# left_revision3_1.net
KiCad netlist of a schematic drawn in EAGLE
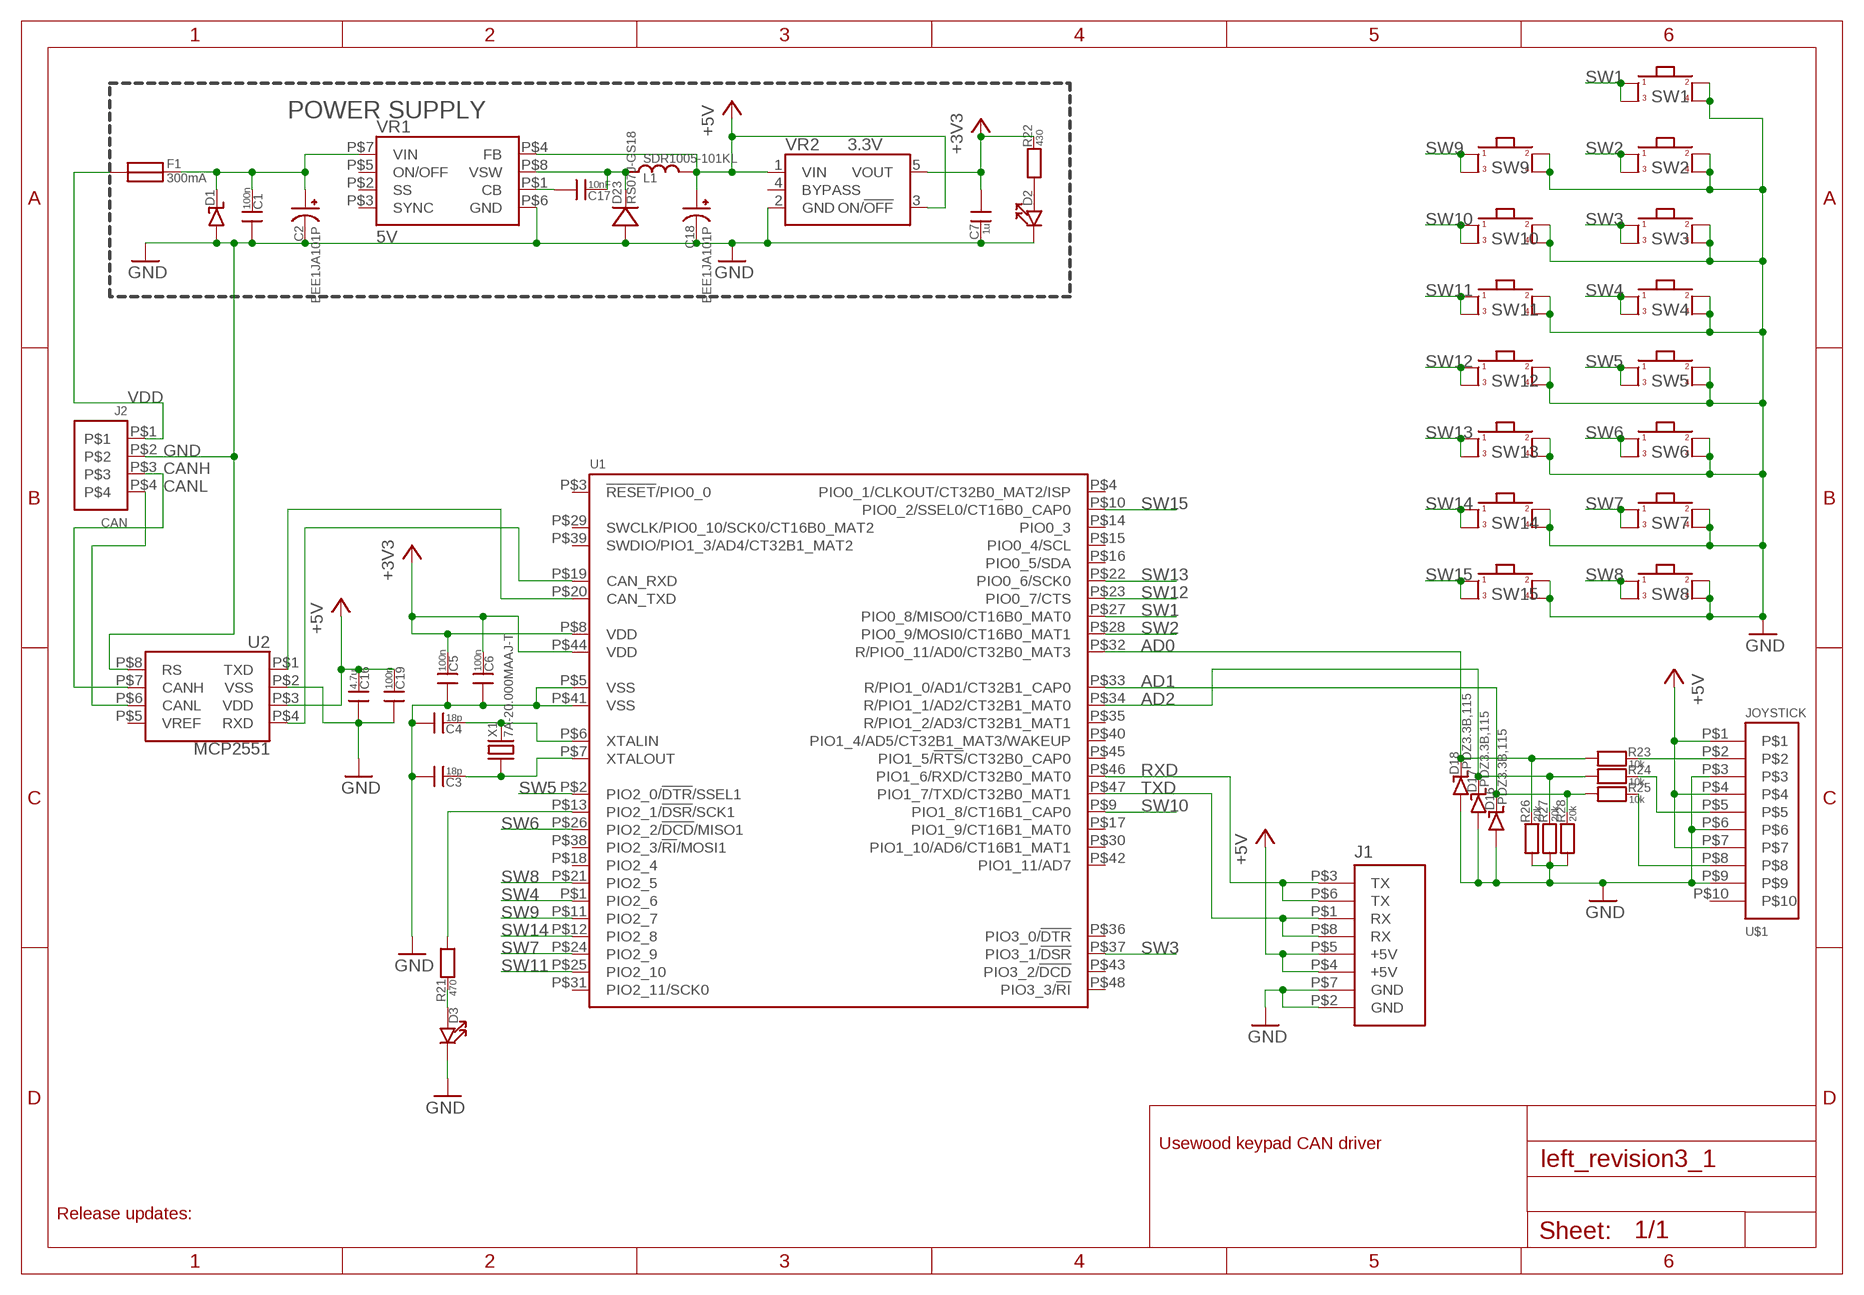
[diagram p0: schematic, sheet 1]

(export (version "E")
  (design (tool "Eeschema 10.0.6"))
  (components
    (comp (ref "C1")
      (value "100n")
      (footprint "eagle-import:0603_SILKSCREEN")
      (libsource (lib "eagle-import") (part "CAP_0603"))
    )
    (comp (ref "C2")
      (value "EEE1JA101P")
      (footprint "eagle-import:CAP_POL_SMD_10X10X10MM")
      (libsource (lib "eagle-import") (part "CAP_POLSMD_10X10X10MM"))
    )
    (comp (ref "C3")
      (value "18p")
      (footprint "eagle-import:0603_SILKSCREEN")
      (libsource (lib "eagle-import") (part "CAP_0603"))
    )
    (comp (ref "C4")
      (value "18p")
      (footprint "eagle-import:0603_SILKSCREEN")
      (libsource (lib "eagle-import") (part "CAP_0603"))
    )
    (comp (ref "C5")
      (value "100n")
      (footprint "eagle-import:0603_SILKSCREEN")
      (libsource (lib "eagle-import") (part "CAP_0603"))
    )
    (comp (ref "C6")
      (value "100n")
      (footprint "eagle-import:0603_SILKSCREEN")
      (libsource (lib "eagle-import") (part "CAP_0603"))
    )
    (comp (ref "C7")
      (value "1u")
      (footprint "eagle-import:0603_SILKSCREEN")
      (libsource (lib "eagle-import") (part "CAP_0603"))
    )
    (comp (ref "C16")
      (value "4.7u")
      (footprint "eagle-import:0603_SILKSCREEN")
      (libsource (lib "eagle-import") (part "CAP_0603"))
    )
    (comp (ref "C17")
      (value "10nF")
      (footprint "eagle-import:0603_SILKSCREEN")
      (libsource (lib "eagle-import") (part "CAP_0603"))
    )
    (comp (ref "C18")
      (value "EEE1JA101P")
      (footprint "eagle-import:CAP_POL_SMD_10X10X10MM")
      (libsource (lib "eagle-import") (part "CAP_POLSMD_10X10X10MM"))
    )
    (comp (ref "C19")
      (value "100n")
      (footprint "eagle-import:0603_SILKSCREEN")
      (libsource (lib "eagle-import") (part "CAP_0603"))
    )
    (comp (ref "D1")
      (value "DIODE_TVSDO-214AA")
      (footprint "eagle-import:DO-214AB")
      (libsource (lib "eagle-import") (part "DIODE_TVSDO-214AA"))
    )
    (comp (ref "D2")
      (value "LED_0603")
      (footprint "eagle-import:0603_SILKSCREEN")
      (libsource (lib "eagle-import") (part "LED_0603"))
    )
    (comp (ref "D3")
      (value "LED_0603")
      (footprint "eagle-import:0603_SILKSCREEN")
      (libsource (lib "eagle-import") (part "LED_0603"))
    )
    (comp (ref "D16")
      (value "PDZ3.3B,115")
      (footprint "eagle-import:SOD123")
      (libsource (lib "eagle-import") (part "DIODE_ZENERSDO123"))
    )
    (comp (ref "D17")
      (value "PDZ3.3B,115")
      (footprint "eagle-import:SOD123")
      (libsource (lib "eagle-import") (part "DIODE_ZENERSDO123"))
    )
    (comp (ref "D18")
      (value "PDZ3.3B,115")
      (footprint "eagle-import:SOD123")
      (libsource (lib "eagle-import") (part "DIODE_ZENERSDO123"))
    )
    (comp (ref "D23")
      (value "RS07J-GS18")
      (footprint "eagle-import:DO219AB")
      (libsource (lib "eagle-import") (part "DIODEDO219AB"))
    )
    (comp (ref "F1")
      (value "300mA")
      (footprint "eagle-import:FUSE_100MA")
      (libsource (lib "eagle-import") (part "FUSE_MC36204_100MA"))
    )
    (comp (ref "J1")
      (value "HEADER_USART_2_SMD")
      (footprint "eagle-import:HEADER_4_2_SMD")
      (libsource (lib "eagle-import") (part "HEADER_USART_2_SMD"))
    )
    (comp (ref "J2")
      (value "CAN")
      (footprint "eagle-import:MOLEX_MICRO_FIT_4WAY_SMD")
      (libsource (lib "eagle-import") (part "MOLEX_MICRO-FIT_4WAY_SMD"))
    )
    (comp (ref "L1")
      (value "SDR1005-101KL")
      (footprint "eagle-import:INDUCTOR_BOURNS_10X13X5MM")
      (libsource (lib "eagle-import") (part "INDUCTORBOURNS_10X13X5MM"))
    )
    (comp (ref "R21")
      (value "470")
      (footprint "eagle-import:0603_SILKSCREEN")
      (libsource (lib "eagle-import") (part "RES_0603"))
    )
    (comp (ref "R22")
      (value "430")
      (footprint "eagle-import:0603_SILKSCREEN")
      (libsource (lib "eagle-import") (part "RES_0603"))
    )
    (comp (ref "R23")
      (value "10k")
      (footprint "eagle-import:0603_SILKSCREEN")
      (libsource (lib "eagle-import") (part "RES_0603"))
    )
    (comp (ref "R24")
      (value "10k")
      (footprint "eagle-import:0603_SILKSCREEN")
      (libsource (lib "eagle-import") (part "RES_0603"))
    )
    (comp (ref "R25")
      (value "10k")
      (footprint "eagle-import:0603_SILKSCREEN")
      (libsource (lib "eagle-import") (part "RES_0603"))
    )
    (comp (ref "R26")
      (value "20k")
      (footprint "eagle-import:0603_SILKSCREEN")
      (libsource (lib "eagle-import") (part "RES_0603"))
    )
    (comp (ref "R27")
      (value "20k")
      (footprint "eagle-import:0603_SILKSCREEN")
      (libsource (lib "eagle-import") (part "RES_0603"))
    )
    (comp (ref "R28")
      (value "20k")
      (footprint "eagle-import:0603_SILKSCREEN")
      (libsource (lib "eagle-import") (part "RES_0603"))
    )
    (comp (ref "SW1")
      (value "SWITCH_KMR231G")
      (footprint "eagle-import:SWITCH_KMR231")
      (libsource (lib "eagle-import") (part "SWITCH_KMR231G"))
    )
    (comp (ref "SW2")
      (value "SWITCH_KMR231G")
      (footprint "eagle-import:SWITCH_KMR231")
      (libsource (lib "eagle-import") (part "SWITCH_KMR231G"))
    )
    (comp (ref "SW3")
      (value "SWITCH_KMR231G")
      (footprint "eagle-import:SWITCH_KMR231")
      (libsource (lib "eagle-import") (part "SWITCH_KMR231G"))
    )
    (comp (ref "SW4")
      (value "SWITCH_KMR231G")
      (footprint "eagle-import:SWITCH_KMR231")
      (libsource (lib "eagle-import") (part "SWITCH_KMR231G"))
    )
    (comp (ref "SW5")
      (value "SWITCH_KMR231G")
      (footprint "eagle-import:SWITCH_KMR231")
      (libsource (lib "eagle-import") (part "SWITCH_KMR231G"))
    )
    (comp (ref "SW6")
      (value "SWITCH_KMR231G")
      (footprint "eagle-import:SWITCH_KMR231")
      (libsource (lib "eagle-import") (part "SWITCH_KMR231G"))
    )
    (comp (ref "SW7")
      (value "SWITCH_KMR231G")
      (footprint "eagle-import:SWITCH_KMR231")
      (libsource (lib "eagle-import") (part "SWITCH_KMR231G"))
    )
    (comp (ref "SW8")
      (value "SWITCH_KMR231G")
      (footprint "eagle-import:SWITCH_KMR231")
      (libsource (lib "eagle-import") (part "SWITCH_KMR231G"))
    )
    (comp (ref "SW9")
      (value "SWITCH_KMR231G")
      (footprint "eagle-import:SWITCH_KMR231")
      (libsource (lib "eagle-import") (part "SWITCH_KMR231G"))
    )
    (comp (ref "SW10")
      (value "SWITCH_KMR231G")
      (footprint "eagle-import:SWITCH_KMR231")
      (libsource (lib "eagle-import") (part "SWITCH_KMR231G"))
    )
    (comp (ref "SW11")
      (value "SWITCH_KMR231G")
      (footprint "eagle-import:SWITCH_KMR231")
      (libsource (lib "eagle-import") (part "SWITCH_KMR231G"))
    )
    (comp (ref "SW12")
      (value "SWITCH_KMR231G")
      (footprint "eagle-import:SWITCH_KMR231")
      (libsource (lib "eagle-import") (part "SWITCH_KMR231G"))
    )
    (comp (ref "SW13")
      (value "SWITCH_KMR231G")
      (footprint "eagle-import:SWITCH_KMR231")
      (libsource (lib "eagle-import") (part "SWITCH_KMR231G"))
    )
    (comp (ref "SW14")
      (value "SWITCH_KMR231G")
      (footprint "eagle-import:SWITCH_KMR231")
      (libsource (lib "eagle-import") (part "SWITCH_KMR231G"))
    )
    (comp (ref "SW15")
      (value "SWITCH_KMR231G")
      (footprint "eagle-import:SWITCH_KMR231")
      (libsource (lib "eagle-import") (part "SWITCH_KMR231G"))
    )
    (comp (ref "U$1")
      (value "JOYSTICK")
      (footprint "eagle-import:MOLEX_MICRO_FIT_10WAY_SMD")
      (libsource (lib "eagle-import") (part "MOLEX_MICRO-FIT_10WAY_SMD"))
    )
    (comp (ref "U1")
      (value "LPC11C14_QFP48")
      (footprint "eagle-import:QFP48")
      (libsource (lib "eagle-import") (part "LPC11C14_QFP48"))
    )
    (comp (ref "U2")
      (value "MCP2551")
      (footprint "eagle-import:SOIC8")
      (libsource (lib "eagle-import") (part "MCP2551_SOIC8"))
    )
    (comp (ref "VR1")
      (value "5V")
      (footprint "eagle-import:SOIC8")
      (libsource (lib "eagle-import") (part "LM2671SOIC8"))
    )
    (comp (ref "VR2")
      (value "3.3V")
      (footprint "eagle-import:SOP5")
      (libsource (lib "eagle-import") (part "REG_LP2985_SOP5"))
    )
    (comp (ref "X1")
      (value "7A-20.000MAAJ-T")
      (footprint "eagle-import:XTAL_SMD_5X3.2")
      (libsource (lib "eagle-import") (part "XTAL_7A-12.000MAAJ-T"))
    )
  )
  (nets
    (net (code "1") (name "+3V3") (class "Default")
      (node (ref "C5") (pin "1") (pinfunction "P$2_1") (pintype "bidirectional"))
      (node (ref "C6") (pin "1") (pinfunction "P$2_1") (pintype "bidirectional"))
      (node (ref "C7") (pin "0") (pinfunction "P$1_0") (pintype "bidirectional"))
      (node (ref "R22") (pin "1") (pinfunction "P$2_1") (pintype "bidirectional"))
      (node (ref "U1") (pin "P$44") (pinfunction "VDD_P$44") (pintype "bidirectional"))
      (node (ref "U1") (pin "P$8") (pinfunction "VDD_P$8") (pintype "bidirectional"))
      (node (ref "VR2") (pin "5") (pinfunction "VOUT_5") (pintype "bidirectional"))
    )
    (net (code "2") (name "+5V") (class "Default")
      (node (ref "C16") (pin "1") (pinfunction "P$2_1") (pintype "bidirectional"))
      (node (ref "C18") (pin "+") (pinfunction "+_+") (pintype "bidirectional"))
      (node (ref "C19") (pin "1") (pinfunction "P$2_1") (pintype "bidirectional"))
      (node (ref "J1") (pin "P$4") (pinfunction "+5V_P$4") (pintype "bidirectional"))
      (node (ref "J1") (pin "P$5") (pinfunction "+5V_P$5") (pintype "bidirectional"))
      (node (ref "L1") (pin "P$2") (pinfunction "P$2_P$2") (pintype "bidirectional"))
      (node (ref "U$1") (pin "P$1") (pinfunction "P$1_P$1") (pintype "bidirectional"))
      (node (ref "U$1") (pin "P$4") (pinfunction "P$4_P$4") (pintype "bidirectional"))
      (node (ref "U$1") (pin "P$7") (pinfunction "P$7_P$7") (pintype "bidirectional"))
      (node (ref "U2") (pin "P$3") (pinfunction "VDD_P$3") (pintype "bidirectional"))
      (node (ref "VR1") (pin "P$4") (pinfunction "FB_P$4") (pintype "bidirectional"))
      (node (ref "VR2") (pin "1") (pinfunction "VIN_1") (pintype "bidirectional"))
      (node (ref "VR2") (pin "3") (pinfunction "ON/~{OFF}_3") (pintype "bidirectional"))
    )
    (net (code "3") (name "/AD0") (class "Default")
      (node (ref "D18") (pin "P$2") (pinfunction "N_P$2") (pintype "bidirectional"))
      (node (ref "R23") (pin "0") (pinfunction "P$1_0") (pintype "bidirectional"))
      (node (ref "R26") (pin "1") (pinfunction "P$2_1") (pintype "bidirectional"))
      (node (ref "U1") (pin "P$32") (pinfunction "R/PIO0_11/AD0/CT32B0_MAT3_P$32") (pintype "bidirectional"))
    )
    (net (code "4") (name "/AD1") (class "Default")
      (node (ref "D16") (pin "P$2") (pinfunction "N_P$2") (pintype "bidirectional"))
      (node (ref "R25") (pin "0") (pinfunction "P$1_0") (pintype "bidirectional"))
      (node (ref "R28") (pin "1") (pinfunction "P$2_1") (pintype "bidirectional"))
      (node (ref "U1") (pin "P$33") (pinfunction "R/PIO1_0/AD1/CT32B1_CAP0_P$33") (pintype "bidirectional"))
    )
    (net (code "5") (name "/AD2") (class "Default")
      (node (ref "D17") (pin "P$2") (pinfunction "N_P$2") (pintype "bidirectional"))
      (node (ref "R24") (pin "0") (pinfunction "P$1_0") (pintype "bidirectional"))
      (node (ref "R27") (pin "1") (pinfunction "P$2_1") (pintype "bidirectional"))
      (node (ref "U1") (pin "P$34") (pinfunction "R/PIO1_1/AD2/CT32B1_MAT0_P$34") (pintype "bidirectional"))
    )
    (net (code "6") (name "/CANH") (class "Default")
      (node (ref "J2") (pin "P$3") (pinfunction "P$3_P$3") (pintype "bidirectional"))
      (node (ref "U2") (pin "P$7") (pinfunction "CANH_P$7") (pintype "bidirectional"))
    )
    (net (code "7") (name "/CANL") (class "Default")
      (node (ref "J2") (pin "P$4") (pinfunction "P$4_P$4") (pintype "bidirectional"))
      (node (ref "U2") (pin "P$6") (pinfunction "CANL_P$6") (pintype "bidirectional"))
    )
    (net (code "8") (name "/RXD") (class "Default")
      (node (ref "J1") (pin "P$3") (pinfunction "TX_P$3") (pintype "bidirectional"))
      (node (ref "J1") (pin "P$6") (pinfunction "TX_P$6") (pintype "bidirectional"))
      (node (ref "U1") (pin "P$46") (pinfunction "PIO1_6/RXD/CT32B0_MAT0_P$46") (pintype "bidirectional"))
    )
    (net (code "9") (name "/SW1") (class "Default")
      (node (ref "SW1") (pin "P$1") (pinfunction "P$1_P$1") (pintype "bidirectional"))
      (node (ref "SW1") (pin "P$3") (pinfunction "P$3_P$3") (pintype "bidirectional"))
      (node (ref "U1") (pin "P$27") (pinfunction "PIO0_8/MISO0/CT16B0_MAT0_P$27") (pintype "bidirectional"))
    )
    (net (code "10") (name "/SW2") (class "Default")
      (node (ref "SW2") (pin "P$1") (pinfunction "P$1_P$1") (pintype "bidirectional"))
      (node (ref "SW2") (pin "P$3") (pinfunction "P$3_P$3") (pintype "bidirectional"))
      (node (ref "U1") (pin "P$28") (pinfunction "PIO0_9/MOSI0/CT16B0_MAT1_P$28") (pintype "bidirectional"))
    )
    (net (code "11") (name "/SW3") (class "Default")
      (node (ref "SW3") (pin "P$1") (pinfunction "P$1_P$1") (pintype "bidirectional"))
      (node (ref "SW3") (pin "P$3") (pinfunction "P$3_P$3") (pintype "bidirectional"))
      (node (ref "U1") (pin "P$37") (pinfunction "PIO3_1/~{DSR}_P$37") (pintype "bidirectional"))
    )
    (net (code "12") (name "/SW4") (class "Default")
      (node (ref "SW4") (pin "P$1") (pinfunction "P$1_P$1") (pintype "bidirectional"))
      (node (ref "SW4") (pin "P$3") (pinfunction "P$3_P$3") (pintype "bidirectional"))
      (node (ref "U1") (pin "P$1") (pinfunction "PIO2_6_P$1") (pintype "bidirectional"))
    )
    (net (code "13") (name "/SW5") (class "Default")
      (node (ref "SW5") (pin "P$1") (pinfunction "P$1_P$1") (pintype "bidirectional"))
      (node (ref "SW5") (pin "P$3") (pinfunction "P$3_P$3") (pintype "bidirectional"))
      (node (ref "U1") (pin "P$2") (pinfunction "PIO2_0/~{DTR}/SSEL1_P$2") (pintype "bidirectional"))
    )
    (net (code "14") (name "/SW6") (class "Default")
      (node (ref "SW6") (pin "P$1") (pinfunction "P$1_P$1") (pintype "bidirectional"))
      (node (ref "SW6") (pin "P$3") (pinfunction "P$3_P$3") (pintype "bidirectional"))
      (node (ref "U1") (pin "P$26") (pinfunction "PIO2_2/~{DCD}/MISO1_P$26") (pintype "bidirectional"))
    )
    (net (code "15") (name "/SW7") (class "Default")
      (node (ref "SW7") (pin "P$1") (pinfunction "P$1_P$1") (pintype "bidirectional"))
      (node (ref "SW7") (pin "P$3") (pinfunction "P$3_P$3") (pintype "bidirectional"))
      (node (ref "U1") (pin "P$24") (pinfunction "PIO2_9_P$24") (pintype "bidirectional"))
    )
    (net (code "16") (name "/SW8") (class "Default")
      (node (ref "SW8") (pin "P$1") (pinfunction "P$1_P$1") (pintype "bidirectional"))
      (node (ref "SW8") (pin "P$3") (pinfunction "P$3_P$3") (pintype "bidirectional"))
      (node (ref "U1") (pin "P$21") (pinfunction "PIO2_5_P$21") (pintype "bidirectional"))
    )
    (net (code "17") (name "/SW9") (class "Default")
      (node (ref "SW9") (pin "P$1") (pinfunction "P$1_P$1") (pintype "bidirectional"))
      (node (ref "SW9") (pin "P$3") (pinfunction "P$3_P$3") (pintype "bidirectional"))
      (node (ref "U1") (pin "P$11") (pinfunction "PIO2_7_P$11") (pintype "bidirectional"))
    )
    (net (code "18") (name "/SW10") (class "Default")
      (node (ref "SW10") (pin "P$1") (pinfunction "P$1_P$1") (pintype "bidirectional"))
      (node (ref "SW10") (pin "P$3") (pinfunction "P$3_P$3") (pintype "bidirectional"))
      (node (ref "U1") (pin "P$9") (pinfunction "PIO1_8/CT16B1_CAP0_P$9") (pintype "bidirectional"))
    )
    (net (code "19") (name "/SW11") (class "Default")
      (node (ref "SW11") (pin "P$1") (pinfunction "P$1_P$1") (pintype "bidirectional"))
      (node (ref "SW11") (pin "P$3") (pinfunction "P$3_P$3") (pintype "bidirectional"))
      (node (ref "U1") (pin "P$25") (pinfunction "PIO2_10_P$25") (pintype "bidirectional"))
    )
    (net (code "20") (name "/SW12") (class "Default")
      (node (ref "SW12") (pin "P$1") (pinfunction "P$1_P$1") (pintype "bidirectional"))
      (node (ref "SW12") (pin "P$3") (pinfunction "P$3_P$3") (pintype "bidirectional"))
      (node (ref "U1") (pin "P$23") (pinfunction "PIO0_7/CTS_P$23") (pintype "bidirectional"))
    )
    (net (code "21") (name "/SW13") (class "Default")
      (node (ref "SW13") (pin "P$1") (pinfunction "P$1_P$1") (pintype "bidirectional"))
      (node (ref "SW13") (pin "P$3") (pinfunction "P$3_P$3") (pintype "bidirectional"))
      (node (ref "U1") (pin "P$22") (pinfunction "PIO0_6/SCK0_P$22") (pintype "bidirectional"))
    )
    (net (code "22") (name "/SW14") (class "Default")
      (node (ref "SW14") (pin "P$1") (pinfunction "P$1_P$1") (pintype "bidirectional"))
      (node (ref "SW14") (pin "P$3") (pinfunction "P$3_P$3") (pintype "bidirectional"))
      (node (ref "U1") (pin "P$12") (pinfunction "PIO2_8_P$12") (pintype "bidirectional"))
    )
    (net (code "23") (name "/SW15") (class "Default")
      (node (ref "SW15") (pin "P$1") (pinfunction "P$1_P$1") (pintype "bidirectional"))
      (node (ref "SW15") (pin "P$3") (pinfunction "P$3_P$3") (pintype "bidirectional"))
      (node (ref "U1") (pin "P$10") (pinfunction "PIO0_2/SSEL0/CT16B0_CAP0_P$10") (pintype "bidirectional"))
    )
    (net (code "24") (name "/TXD") (class "Default")
      (node (ref "J1") (pin "P$1") (pinfunction "RX_P$1") (pintype "bidirectional"))
      (node (ref "J1") (pin "P$8") (pinfunction "RX_P$8") (pintype "bidirectional"))
      (node (ref "U1") (pin "P$47") (pinfunction "PIO1_7/TXD/CT32B0_MAT1_P$47") (pintype "bidirectional"))
    )
    (net (code "25") (name "/VDD") (class "Default")
      (node (ref "F1") (pin "P$1") (pinfunction "P$1_P$1") (pintype "bidirectional"))
      (node (ref "J2") (pin "P$1") (pinfunction "P$1_P$1") (pintype "bidirectional"))
    )
    (net (code "26") (name "GND") (class "Default")
      (node (ref "C1") (pin "0") (pinfunction "P$1_0") (pintype "bidirectional"))
      (node (ref "C16") (pin "0") (pinfunction "P$1_0") (pintype "bidirectional"))
      (node (ref "C18") (pin "-") (pinfunction "-_-") (pintype "bidirectional"))
      (node (ref "C19") (pin "0") (pinfunction "P$1_0") (pintype "bidirectional"))
      (node (ref "C2") (pin "-") (pinfunction "-_-") (pintype "bidirectional"))
      (node (ref "C3") (pin "0") (pinfunction "P$1_0") (pintype "bidirectional"))
      (node (ref "C4") (pin "0") (pinfunction "P$1_0") (pintype "bidirectional"))
      (node (ref "C5") (pin "0") (pinfunction "P$1_0") (pintype "bidirectional"))
      (node (ref "C6") (pin "0") (pinfunction "P$1_0") (pintype "bidirectional"))
      (node (ref "C7") (pin "1") (pinfunction "P$2_1") (pintype "bidirectional"))
      (node (ref "D1") (pin "P$1") (pinfunction "P_P$1") (pintype "bidirectional"))
      (node (ref "D16") (pin "P$1") (pinfunction "P_P$1") (pintype "bidirectional"))
      (node (ref "D17") (pin "P$1") (pinfunction "P_P$1") (pintype "bidirectional"))
      (node (ref "D18") (pin "P$1") (pinfunction "P_P$1") (pintype "bidirectional"))
      (node (ref "D2") (pin "1") (pinfunction "1_1") (pintype "bidirectional"))
      (node (ref "D23") (pin "P$1") (pinfunction "P_P$1") (pintype "bidirectional"))
      (node (ref "D3") (pin "1") (pinfunction "1_1") (pintype "bidirectional"))
      (node (ref "J1") (pin "P$2") (pinfunction "GND_P$2") (pintype "bidirectional"))
      (node (ref "J1") (pin "P$7") (pinfunction "GND_P$7") (pintype "bidirectional"))
      (node (ref "J2") (pin "P$2") (pinfunction "P$2_P$2") (pintype "bidirectional"))
      (node (ref "R26") (pin "0") (pinfunction "P$1_0") (pintype "bidirectional"))
      (node (ref "R27") (pin "0") (pinfunction "P$1_0") (pintype "bidirectional"))
      (node (ref "R28") (pin "0") (pinfunction "P$1_0") (pintype "bidirectional"))
      (node (ref "SW1") (pin "P$2") (pinfunction "P$2_P$2") (pintype "bidirectional"))
      (node (ref "SW1") (pin "P$4") (pinfunction "P$4_P$4") (pintype "bidirectional"))
      (node (ref "SW10") (pin "P$2") (pinfunction "P$2_P$2") (pintype "bidirectional"))
      (node (ref "SW10") (pin "P$4") (pinfunction "P$4_P$4") (pintype "bidirectional"))
      (node (ref "SW11") (pin "P$2") (pinfunction "P$2_P$2") (pintype "bidirectional"))
      (node (ref "SW11") (pin "P$4") (pinfunction "P$4_P$4") (pintype "bidirectional"))
      (node (ref "SW12") (pin "P$2") (pinfunction "P$2_P$2") (pintype "bidirectional"))
      (node (ref "SW12") (pin "P$4") (pinfunction "P$4_P$4") (pintype "bidirectional"))
      (node (ref "SW13") (pin "P$2") (pinfunction "P$2_P$2") (pintype "bidirectional"))
      (node (ref "SW13") (pin "P$4") (pinfunction "P$4_P$4") (pintype "bidirectional"))
      (node (ref "SW14") (pin "P$2") (pinfunction "P$2_P$2") (pintype "bidirectional"))
      (node (ref "SW14") (pin "P$4") (pinfunction "P$4_P$4") (pintype "bidirectional"))
      (node (ref "SW15") (pin "P$2") (pinfunction "P$2_P$2") (pintype "bidirectional"))
      (node (ref "SW15") (pin "P$4") (pinfunction "P$4_P$4") (pintype "bidirectional"))
      (node (ref "SW2") (pin "P$2") (pinfunction "P$2_P$2") (pintype "bidirectional"))
      (node (ref "SW2") (pin "P$4") (pinfunction "P$4_P$4") (pintype "bidirectional"))
      (node (ref "SW3") (pin "P$2") (pinfunction "P$2_P$2") (pintype "bidirectional"))
      (node (ref "SW3") (pin "P$4") (pinfunction "P$4_P$4") (pintype "bidirectional"))
      (node (ref "SW4") (pin "P$2") (pinfunction "P$2_P$2") (pintype "bidirectional"))
      (node (ref "SW4") (pin "P$4") (pinfunction "P$4_P$4") (pintype "bidirectional"))
      (node (ref "SW5") (pin "P$2") (pinfunction "P$2_P$2") (pintype "bidirectional"))
      (node (ref "SW5") (pin "P$4") (pinfunction "P$4_P$4") (pintype "bidirectional"))
      (node (ref "SW6") (pin "P$2") (pinfunction "P$2_P$2") (pintype "bidirectional"))
      (node (ref "SW6") (pin "P$4") (pinfunction "P$4_P$4") (pintype "bidirectional"))
      (node (ref "SW7") (pin "P$2") (pinfunction "P$2_P$2") (pintype "bidirectional"))
      (node (ref "SW7") (pin "P$4") (pinfunction "P$4_P$4") (pintype "bidirectional"))
      (node (ref "SW8") (pin "P$2") (pinfunction "P$2_P$2") (pintype "bidirectional"))
      (node (ref "SW8") (pin "P$4") (pinfunction "P$4_P$4") (pintype "bidirectional"))
      (node (ref "SW9") (pin "P$2") (pinfunction "P$2_P$2") (pintype "bidirectional"))
      (node (ref "SW9") (pin "P$4") (pinfunction "P$4_P$4") (pintype "bidirectional"))
      (node (ref "U$1") (pin "P$3") (pinfunction "P$3_P$3") (pintype "bidirectional"))
      (node (ref "U$1") (pin "P$6") (pinfunction "P$6_P$6") (pintype "bidirectional"))
      (node (ref "U$1") (pin "P$9") (pinfunction "P$9_P$9") (pintype "bidirectional"))
      (node (ref "U1") (pin "P$41") (pinfunction "VSS_P$41") (pintype "bidirectional"))
      (node (ref "U1") (pin "P$5") (pinfunction "VSS_P$5") (pintype "bidirectional"))
      (node (ref "U2") (pin "P$2") (pinfunction "VSS_P$2") (pintype "bidirectional"))
      (node (ref "U2") (pin "P$8") (pinfunction "RS_P$8") (pintype "bidirectional"))
      (node (ref "VR1") (pin "P$6") (pinfunction "GND_P$6") (pintype "bidirectional"))
      (node (ref "VR2") (pin "2") (pinfunction "GND_2") (pintype "bidirectional"))
    )
    (net (code "27") (name "Net-(C1-P$2)") (class "Default")
      (node (ref "C1") (pin "1") (pinfunction "P$2_1") (pintype "bidirectional"))
      (node (ref "C2") (pin "+") (pinfunction "+_+") (pintype "bidirectional"))
      (node (ref "D1") (pin "P$2") (pinfunction "N_P$2") (pintype "bidirectional"))
      (node (ref "F1") (pin "P$2") (pinfunction "P$2_P$2") (pintype "bidirectional"))
      (node (ref "VR1") (pin "P$7") (pinfunction "VIN_P$7") (pintype "bidirectional"))
    )
    (net (code "28") (name "Net-(C3-P$2)") (class "Default")
      (node (ref "C3") (pin "1") (pinfunction "P$2_1") (pintype "bidirectional"))
      (node (ref "U1") (pin "P$7") (pinfunction "XTALOUT_P$7") (pintype "bidirectional"))
      (node (ref "X1") (pin "P$1") (pinfunction "P$1_P$1") (pintype "bidirectional"))
    )
    (net (code "29") (name "Net-(C4-P$2)") (class "Default")
      (node (ref "C4") (pin "1") (pinfunction "P$2_1") (pintype "bidirectional"))
      (node (ref "U1") (pin "P$6") (pinfunction "XTALIN_P$6") (pintype "bidirectional"))
      (node (ref "X1") (pin "P$2") (pinfunction "P$2_P$2") (pintype "bidirectional"))
    )
    (net (code "30") (name "Net-(C17-P$1)") (class "Default")
      (node (ref "C17") (pin "0") (pinfunction "P$1_0") (pintype "bidirectional"))
      (node (ref "VR1") (pin "P$1") (pinfunction "CB_P$1") (pintype "bidirectional"))
    )
    (net (code "31") (name "Net-(C17-P$2)") (class "Default")
      (node (ref "C17") (pin "1") (pinfunction "P$2_1") (pintype "bidirectional"))
      (node (ref "D23") (pin "P$2") (pinfunction "N_P$2") (pintype "bidirectional"))
      (node (ref "L1") (pin "P$1") (pinfunction "P$1_P$1") (pintype "bidirectional"))
      (node (ref "VR1") (pin "P$8") (pinfunction "VSW_P$8") (pintype "bidirectional"))
    )
    (net (code "32") (name "Net-(R21-P$1)") (class "Default")
      (node (ref "R21") (pin "0") (pinfunction "P$1_0") (pintype "bidirectional"))
      (node (ref "U1") (pin "P$13") (pinfunction "PIO2_1/~{DSR}/SCK1_P$13") (pintype "bidirectional"))
    )
    (net (code "33") (name "Net-(R21-P$2)") (class "Default")
      (node (ref "D3") (pin "0") (pinfunction "0_0") (pintype "bidirectional"))
      (node (ref "R21") (pin "1") (pinfunction "P$2_1") (pintype "bidirectional"))
    )
    (net (code "34") (name "Net-(R22-P$1)") (class "Default")
      (node (ref "D2") (pin "0") (pinfunction "0_0") (pintype "bidirectional"))
      (node (ref "R22") (pin "0") (pinfunction "P$1_0") (pintype "bidirectional"))
    )
    (net (code "35") (name "Net-(R23-P$2)") (class "Default")
      (node (ref "R23") (pin "1") (pinfunction "P$2_1") (pintype "bidirectional"))
      (node (ref "U$1") (pin "P$2") (pinfunction "P$2_P$2") (pintype "bidirectional"))
    )
    (net (code "36") (name "Net-(R24-P$2)") (class "Default")
      (node (ref "R24") (pin "1") (pinfunction "P$2_1") (pintype "bidirectional"))
      (node (ref "U$1") (pin "P$5") (pinfunction "P$5_P$5") (pintype "bidirectional"))
    )
    (net (code "37") (name "Net-(R25-P$2)") (class "Default")
      (node (ref "R25") (pin "1") (pinfunction "P$2_1") (pintype "bidirectional"))
      (node (ref "U$1") (pin "P$8") (pinfunction "P$8_P$8") (pintype "bidirectional"))
    )
    (net (code "38") (name "Net-(U1-CAN_RXD)") (class "Default")
      (node (ref "U1") (pin "P$19") (pinfunction "CAN_RXD_P$19") (pintype "bidirectional"))
      (node (ref "U2") (pin "P$4") (pinfunction "RXD_P$4") (pintype "bidirectional"))
    )
    (net (code "39") (name "Net-(U1-CAN_TXD)") (class "Default")
      (node (ref "U1") (pin "P$20") (pinfunction "CAN_TXD_P$20") (pintype "bidirectional"))
      (node (ref "U2") (pin "P$1") (pinfunction "TXD_P$1") (pintype "bidirectional"))
    )
    (net (code "40") (name "unconnected-(U$1-PadP$10)") (class "Default")
      (node (ref "U$1") (pin "P$10") (pinfunction "P$10_P$10") (pintype "bidirectional"))
    )
    (net (code "41") (name "unconnected-(U1-PIO0_1{slash}CLKOUT{slash}CT32B0_MAT2{slash}ISP-PadP$4)") (class "Default")
      (node (ref "U1") (pin "P$4") (pinfunction "PIO0_1/CLKOUT/CT32B0_MAT2/ISP_P$4") (pintype "bidirectional"))
    )
    (net (code "42") (name "unconnected-(U1-PIO0_3-PadP$14)") (class "Default")
      (node (ref "U1") (pin "P$14") (pinfunction "PIO0_3_P$14") (pintype "bidirectional"))
    )
    (net (code "43") (name "unconnected-(U1-PIO0_4{slash}SCL-PadP$15)") (class "Default")
      (node (ref "U1") (pin "P$15") (pinfunction "PIO0_4/SCL_P$15") (pintype "bidirectional"))
    )
    (net (code "44") (name "unconnected-(U1-PIO0_5{slash}SDA-PadP$16)") (class "Default")
      (node (ref "U1") (pin "P$16") (pinfunction "PIO0_5/SDA_P$16") (pintype "bidirectional"))
    )
    (net (code "45") (name "unconnected-(U1-PIO1_4{slash}AD5{slash}CT32B1_MAT3{slash}WAKEUP-PadP$40)") (class "Default")
      (node (ref "U1") (pin "P$40") (pinfunction "PIO1_4/AD5/CT32B1_MAT3/WAKEUP_P$40") (pintype "bidirectional"))
    )
    (net (code "46") (name "unconnected-(U1-PIO1_5{slash}~{RTS}{slash}CT32B0_CAP0-PadP$45)") (class "Default")
      (node (ref "U1") (pin "P$45") (pinfunction "PIO1_5/~{RTS}/CT32B0_CAP0_P$45") (pintype "bidirectional"))
    )
    (net (code "47") (name "unconnected-(U1-PIO1_9{slash}CT16B1_MAT0-PadP$17)") (class "Default")
      (node (ref "U1") (pin "P$17") (pinfunction "PIO1_9/CT16B1_MAT0_P$17") (pintype "bidirectional"))
    )
    (net (code "48") (name "unconnected-(U1-PIO1_10{slash}AD6{slash}CT16B1_MAT1-PadP$30)") (class "Default")
      (node (ref "U1") (pin "P$30") (pinfunction "PIO1_10/AD6/CT16B1_MAT1_P$30") (pintype "bidirectional"))
    )
    (net (code "49") (name "unconnected-(U1-PIO1_11{slash}AD7-PadP$42)") (class "Default")
      (node (ref "U1") (pin "P$42") (pinfunction "PIO1_11/AD7_P$42") (pintype "bidirectional"))
    )
    (net (code "50") (name "unconnected-(U1-PIO2_3{slash}~{RI}{slash}MOSI1-PadP$38)") (class "Default")
      (node (ref "U1") (pin "P$38") (pinfunction "PIO2_3/~{RI}/MOSI1_P$38") (pintype "bidirectional"))
    )
    (net (code "51") (name "unconnected-(U1-PIO2_4-PadP$18)") (class "Default")
      (node (ref "U1") (pin "P$18") (pinfunction "PIO2_4_P$18") (pintype "bidirectional"))
    )
    (net (code "52") (name "unconnected-(U1-PIO2_11{slash}SCK0-PadP$31)") (class "Default")
      (node (ref "U1") (pin "P$31") (pinfunction "PIO2_11/SCK0_P$31") (pintype "bidirectional"))
    )
    (net (code "53") (name "unconnected-(U1-PIO3_0{slash}~{DTR}-PadP$36)") (class "Default")
      (node (ref "U1") (pin "P$36") (pinfunction "PIO3_0/~{DTR}_P$36") (pintype "bidirectional"))
    )
    (net (code "54") (name "unconnected-(U1-PIO3_2{slash}~{DCD}-PadP$43)") (class "Default")
      (node (ref "U1") (pin "P$43") (pinfunction "PIO3_2/~{DCD}_P$43") (pintype "bidirectional"))
    )
    (net (code "55") (name "unconnected-(U1-PIO3_3{slash}~{RI}-PadP$48)") (class "Default")
      (node (ref "U1") (pin "P$48") (pinfunction "PIO3_3/~{RI}_P$48") (pintype "bidirectional"))
    )
    (net (code "56") (name "unconnected-(U1-R{slash}PIO1_2{slash}AD3{slash}CT32B1_MAT1-PadP$35)") (class "Default")
      (node (ref "U1") (pin "P$35") (pinfunction "R/PIO1_2/AD3/CT32B1_MAT1_P$35") (pintype "bidirectional"))
    )
    (net (code "57") (name "unconnected-(U1-SWCLK{slash}PIO0_10{slash}SCK0{slash}CT16B0_MAT2-PadP$29)") (class "Default")
      (node (ref "U1") (pin "P$29") (pinfunction "SWCLK/PIO0_10/SCK0/CT16B0_MAT2_P$29") (pintype "bidirectional"))
    )
    (net (code "58") (name "unconnected-(U1-SWDIO{slash}PIO1_3{slash}AD4{slash}CT32B1_MAT2-PadP$39)") (class "Default")
      (node (ref "U1") (pin "P$39") (pinfunction "SWDIO/PIO1_3/AD4/CT32B1_MAT2_P$39") (pintype "bidirectional"))
    )
    (net (code "59") (name "unconnected-(U1-~{RESET}{slash}PIO0_0-PadP$3)") (class "Default")
      (node (ref "U1") (pin "P$3") (pinfunction "~{RESET}/PIO0_0_P$3") (pintype "bidirectional"))
    )
    (net (code "60") (name "unconnected-(U2-VREF-PadP$5)") (class "Default")
      (node (ref "U2") (pin "P$5") (pinfunction "VREF_P$5") (pintype "bidirectional"))
    )
    (net (code "61") (name "unconnected-(VR1-ON{slash}OFF-PadP$5)") (class "Default")
      (node (ref "VR1") (pin "P$5") (pinfunction "ON/OFF_P$5") (pintype "bidirectional"))
    )
    (net (code "62") (name "unconnected-(VR1-SS-PadP$2)") (class "Default")
      (node (ref "VR1") (pin "P$2") (pinfunction "SS_P$2") (pintype "bidirectional"))
    )
    (net (code "63") (name "unconnected-(VR1-SYNC-PadP$3)") (class "Default")
      (node (ref "VR1") (pin "P$3") (pinfunction "SYNC_P$3") (pintype "bidirectional"))
    )
    (net (code "64") (name "unconnected-(VR2-BYPASS-Pad4)") (class "Default")
      (node (ref "VR2") (pin "4") (pinfunction "BYPASS_4") (pintype "bidirectional"))
    )
  )
)
